# pink-0.net
KiCad netlist of a schematic drawn in EAGLE
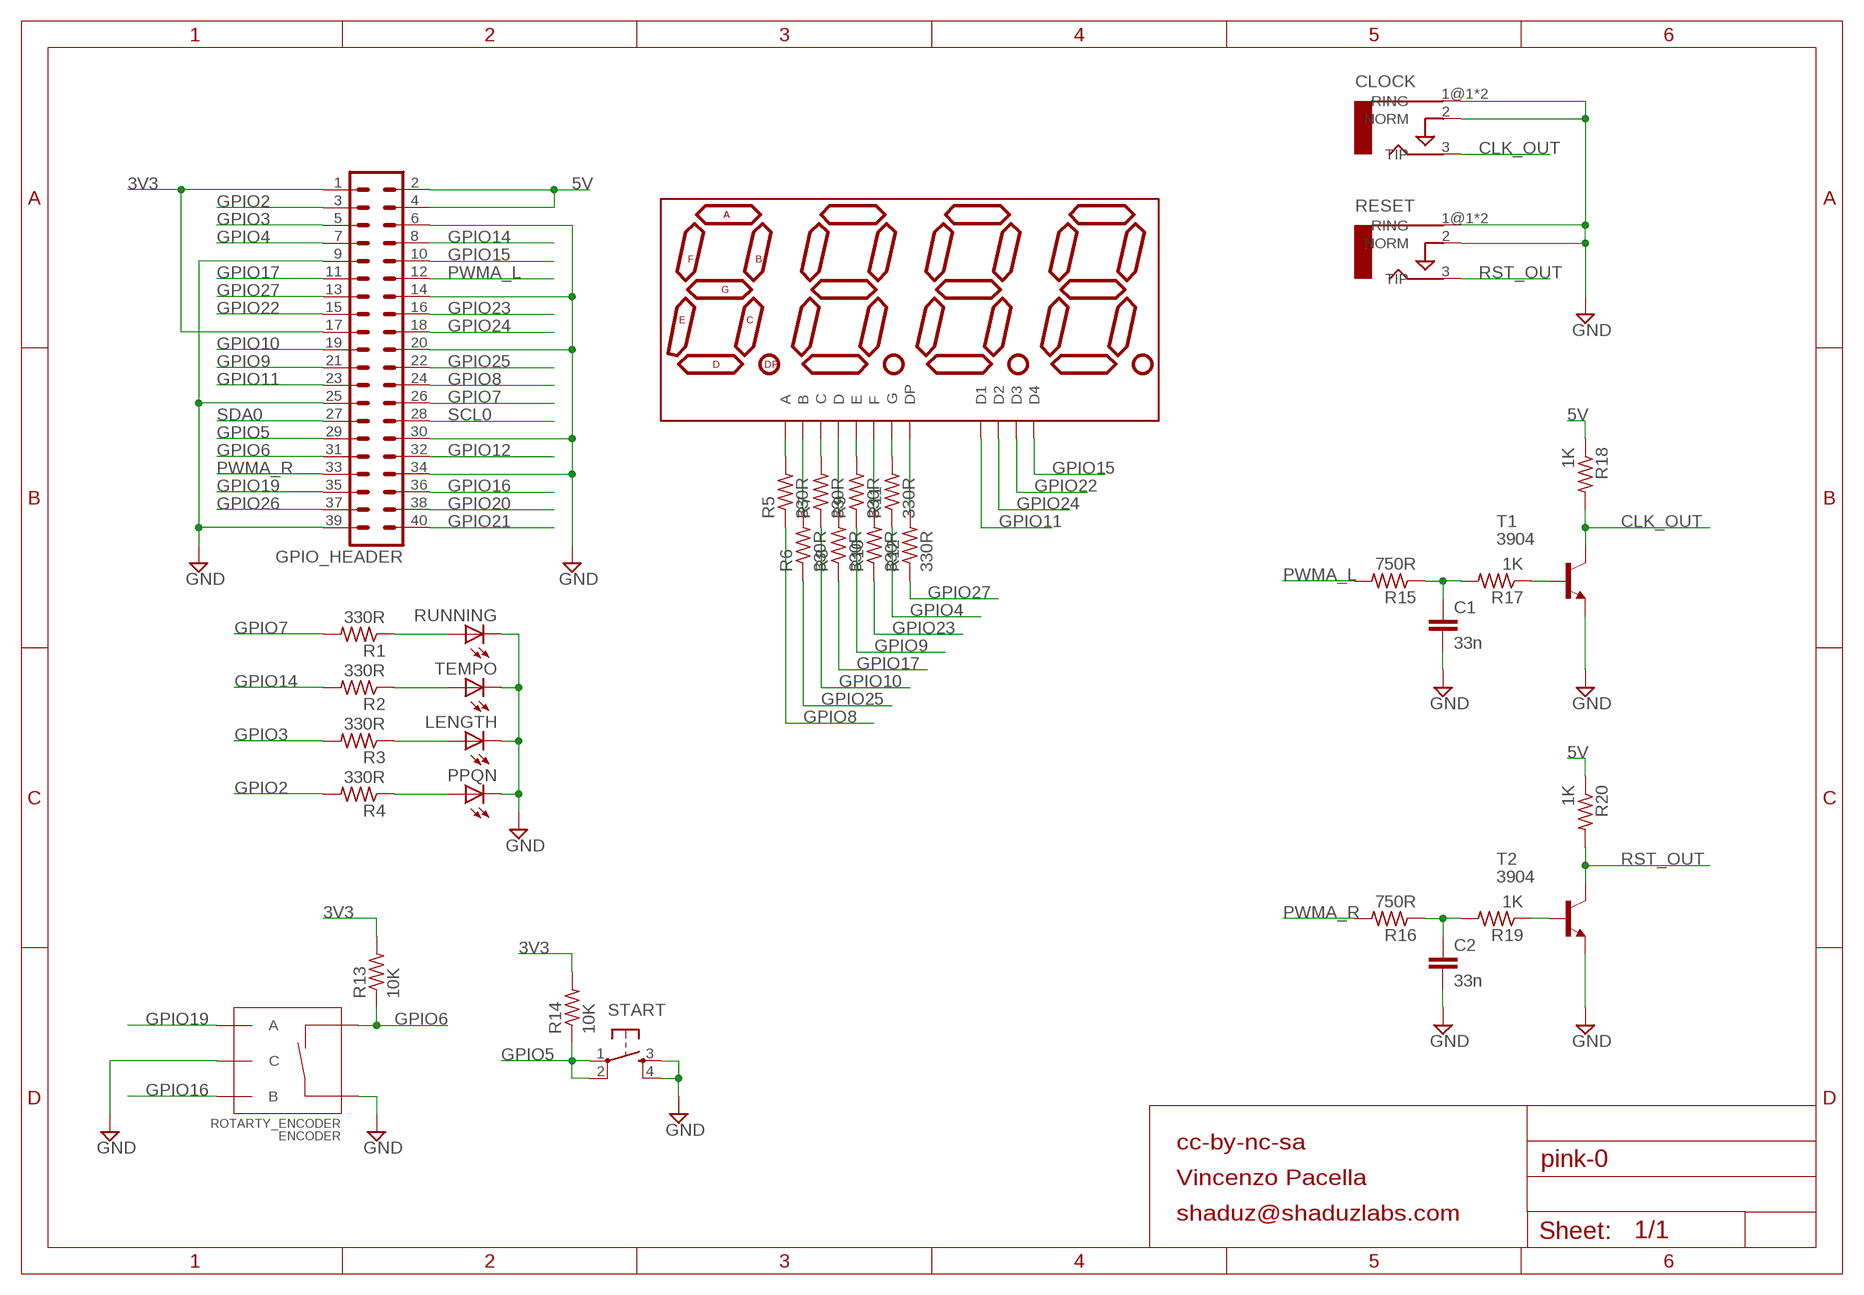
[diagram p0: schematic, sheet 1]

(export (version "E")
  (design (tool "Eeschema 10.0.6"))
  (components
    (comp (ref "C1")
      (value "33n")
      (footprint "eagle-import:0603-CAP")
      (libsource (lib "eagle-import") (part "CAP0603-CAP"))
    )
    (comp (ref "C2")
      (value "33n")
      (footprint "eagle-import:0603-CAP")
      (libsource (lib "eagle-import") (part "CAP0603-CAP"))
    )
    (comp (ref "CLOCK")
      (value "AUDIO-JACKERTHENVAR")
      (footprint "eagle-import:ERTHENVAR-JACK")
      (libsource (lib "eagle-import") (part "AUDIO-JACKERTHENVAR"))
    )
    (comp (ref "DISP1")
      (value "QDSP6064")
      (footprint "eagle-import:DIL12")
      (libsource (lib "eagle-import") (part "7-SEGMENT-4DIGIT-COUNTER-HP-BUBBLE"))
    )
    (comp (ref "ENCODER")
      (value "ROTARTY_ENCODER")
      (footprint "eagle-import:ROTARY_ENC_PLAIN")
      (libsource (lib "eagle-import") (part "ROTARTY_ENCODER"))
    )
    (comp (ref "GPIO_HEADER")
      (value "PIZERO_THROUGH_HOLE")
      (footprint "eagle-import:PIZERO_THOUGH_HOLE")
      (libsource (lib "eagle-import") (part "PIZERO_THROUGH_HOLE"))
    )
    (comp (ref "LENGTH")
      (value "LED0603")
      (footprint "eagle-import:LED-0603")
      (libsource (lib "eagle-import") (part "LED0603"))
    )
    (comp (ref "PPQN")
      (value "LED0603")
      (footprint "eagle-import:LED-0603")
      (libsource (lib "eagle-import") (part "LED0603"))
    )
    (comp (ref "R1")
      (value "330R")
      (footprint "eagle-import:R0402")
      (libsource (lib "eagle-import") (part "R-US_R0402"))
    )
    (comp (ref "R2")
      (value "330R")
      (footprint "eagle-import:R0402")
      (libsource (lib "eagle-import") (part "R-US_R0402"))
    )
    (comp (ref "R3")
      (value "330R")
      (footprint "eagle-import:R0402")
      (libsource (lib "eagle-import") (part "R-US_R0402"))
    )
    (comp (ref "R4")
      (value "330R")
      (footprint "eagle-import:R0402")
      (libsource (lib "eagle-import") (part "R-US_R0402"))
    )
    (comp (ref "R5")
      (value "330R")
      (footprint "eagle-import:R0402")
      (libsource (lib "eagle-import") (part "R-US_R0402"))
    )
    (comp (ref "R6")
      (value "330R")
      (footprint "eagle-import:R0402")
      (libsource (lib "eagle-import") (part "R-US_R0402"))
    )
    (comp (ref "R7")
      (value "330R")
      (footprint "eagle-import:R0402")
      (libsource (lib "eagle-import") (part "R-US_R0402"))
    )
    (comp (ref "R8")
      (value "330R")
      (footprint "eagle-import:R0402")
      (libsource (lib "eagle-import") (part "R-US_R0402"))
    )
    (comp (ref "R9")
      (value "330R")
      (footprint "eagle-import:R0402")
      (libsource (lib "eagle-import") (part "R-US_R0402"))
    )
    (comp (ref "R10")
      (value "330R")
      (footprint "eagle-import:R0402")
      (libsource (lib "eagle-import") (part "R-US_R0402"))
    )
    (comp (ref "R11")
      (value "330R")
      (footprint "eagle-import:R0402")
      (libsource (lib "eagle-import") (part "R-US_R0402"))
    )
    (comp (ref "R12")
      (value "330R")
      (footprint "eagle-import:R0402")
      (libsource (lib "eagle-import") (part "R-US_R0402"))
    )
    (comp (ref "R13")
      (value "10K")
      (footprint "eagle-import:R0402")
      (libsource (lib "eagle-import") (part "R-US_R0402"))
    )
    (comp (ref "R14")
      (value "10K")
      (footprint "eagle-import:R0402")
      (libsource (lib "eagle-import") (part "R-US_R0402"))
    )
    (comp (ref "R15")
      (value "750R")
      (footprint "eagle-import:R0402")
      (libsource (lib "eagle-import") (part "R-US_R0402"))
    )
    (comp (ref "R16")
      (value "750R")
      (footprint "eagle-import:R0402")
      (libsource (lib "eagle-import") (part "R-US_R0402"))
    )
    (comp (ref "R17")
      (value "1K")
      (footprint "eagle-import:R0402")
      (libsource (lib "eagle-import") (part "R-US_R0402"))
    )
    (comp (ref "R18")
      (value "1K")
      (footprint "eagle-import:R0402")
      (libsource (lib "eagle-import") (part "R-US_R0402"))
    )
    (comp (ref "R19")
      (value "1K")
      (footprint "eagle-import:R0402")
      (libsource (lib "eagle-import") (part "R-US_R0402"))
    )
    (comp (ref "R20")
      (value "1K")
      (footprint "eagle-import:R0402")
      (libsource (lib "eagle-import") (part "R-US_R0402"))
    )
    (comp (ref "RESET")
      (value "AUDIO-JACKERTHENVAR")
      (footprint "eagle-import:ERTHENVAR-JACK")
      (libsource (lib "eagle-import") (part "AUDIO-JACKERTHENVAR"))
    )
    (comp (ref "RUNNING")
      (value "LED0603")
      (footprint "eagle-import:LED-0603")
      (libsource (lib "eagle-import") (part "LED0603"))
    )
    (comp (ref "START")
      (value "TAC_SWITCHPTH")
      (footprint "eagle-import:TACTILE-PTH")
      (libsource (lib "eagle-import") (part "TAC_SWITCHPTH"))
    )
    (comp (ref "T1")
      (value "3904")
      (footprint "eagle-import:SOT23-BEC")
      (libsource (lib "eagle-import") (part "-NPN-SOT23-BECMMBT3904LT1"))
    )
    (comp (ref "T2")
      (value "3904")
      (footprint "eagle-import:SOT23-BEC")
      (libsource (lib "eagle-import") (part "-NPN-SOT23-BECMMBT3904LT1"))
    )
    (comp (ref "TEMPO")
      (value "LED0603")
      (footprint "eagle-import:LED-0603")
      (libsource (lib "eagle-import") (part "LED0603"))
    )
  )
  (nets
    (net (code "1") (name "/3V3") (class "Default")
      (node (ref "GPIO_HEADER") (pin "1") (pinfunction "1_1") (pintype "passive"))
      (node (ref "GPIO_HEADER") (pin "17") (pinfunction "17_17") (pintype "passive"))
      (node (ref "R13") (pin "2") (pinfunction "2_2") (pintype "passive"))
      (node (ref "R14") (pin "2") (pinfunction "2_2") (pintype "passive"))
    )
    (net (code "2") (name "/5V") (class "Default")
      (node (ref "GPIO_HEADER") (pin "2") (pinfunction "2_2") (pintype "passive"))
      (node (ref "GPIO_HEADER") (pin "4") (pinfunction "4_4") (pintype "passive"))
      (node (ref "R18") (pin "1") (pinfunction "1_1") (pintype "passive"))
      (node (ref "R20") (pin "1") (pinfunction "1_1") (pintype "passive"))
    )
    (net (code "3") (name "/CLK_OUT") (class "Default")
      (node (ref "CLOCK") (pin "3") (pinfunction "TIP_3") (pintype "bidirectional"))
      (node (ref "R18") (pin "2") (pinfunction "2_2") (pintype "passive"))
      (node (ref "T1") (pin "C") (pinfunction "C_C") (pintype "passive"))
    )
    (net (code "4") (name "/GPIO2") (class "Default")
      (node (ref "GPIO_HEADER") (pin "3") (pinfunction "3_3") (pintype "passive"))
      (node (ref "R4") (pin "2") (pinfunction "2_2") (pintype "passive"))
    )
    (net (code "5") (name "/GPIO3") (class "Default")
      (node (ref "GPIO_HEADER") (pin "5") (pinfunction "5_5") (pintype "passive"))
      (node (ref "R3") (pin "2") (pinfunction "2_2") (pintype "passive"))
    )
    (net (code "6") (name "/GPIO4") (class "Default")
      (node (ref "GPIO_HEADER") (pin "7") (pinfunction "7_7") (pintype "passive"))
      (node (ref "R11") (pin "1") (pinfunction "1_1") (pintype "passive"))
    )
    (net (code "7") (name "/GPIO5") (class "Default")
      (node (ref "GPIO_HEADER") (pin "29") (pinfunction "29_29") (pintype "passive"))
      (node (ref "R14") (pin "1") (pinfunction "1_1") (pintype "passive"))
      (node (ref "START") (pin "1") (pinfunction "1_1") (pintype "passive"))
      (node (ref "START") (pin "2") (pinfunction "2_2") (pintype "passive"))
    )
    (net (code "8") (name "/GPIO6") (class "Default")
      (node (ref "ENCODER") (pin "SW-") (pinfunction "SW-_SW-") (pintype "bidirectional"))
      (node (ref "GPIO_HEADER") (pin "31") (pinfunction "31_31") (pintype "passive"))
      (node (ref "R13") (pin "1") (pinfunction "1_1") (pintype "passive"))
    )
    (net (code "9") (name "/GPIO7") (class "Default")
      (node (ref "GPIO_HEADER") (pin "26") (pinfunction "26_26") (pintype "passive"))
      (node (ref "R1") (pin "2") (pinfunction "2_2") (pintype "passive"))
    )
    (net (code "10") (name "/GPIO8") (class "Default")
      (node (ref "GPIO_HEADER") (pin "24") (pinfunction "24_24") (pintype "passive"))
      (node (ref "R5") (pin "1") (pinfunction "1_1") (pintype "passive"))
    )
    (net (code "11") (name "/GPIO9") (class "Default")
      (node (ref "GPIO_HEADER") (pin "21") (pinfunction "21_21") (pintype "passive"))
      (node (ref "R9") (pin "1") (pinfunction "1_1") (pintype "passive"))
    )
    (net (code "12") (name "/GPIO10") (class "Default")
      (node (ref "GPIO_HEADER") (pin "19") (pinfunction "19_19") (pintype "passive"))
      (node (ref "R7") (pin "1") (pinfunction "1_1") (pintype "passive"))
    )
    (net (code "13") (name "/GPIO11") (class "Default")
      (node (ref "DISP1") (pin "1") (pinfunction "D1_1") (pintype "bidirectional"))
      (node (ref "GPIO_HEADER") (pin "23") (pinfunction "23_23") (pintype "passive"))
    )
    (net (code "14") (name "/GPIO12") (class "Default")
      (node (ref "GPIO_HEADER") (pin "32") (pinfunction "32_32") (pintype "passive"))
    )
    (net (code "15") (name "/GPIO14") (class "Default")
      (node (ref "GPIO_HEADER") (pin "8") (pinfunction "8_8") (pintype "passive"))
      (node (ref "R2") (pin "2") (pinfunction "2_2") (pintype "passive"))
    )
    (net (code "16") (name "/GPIO15") (class "Default")
      (node (ref "DISP1") (pin "6") (pinfunction "D4_6") (pintype "bidirectional"))
      (node (ref "GPIO_HEADER") (pin "10") (pinfunction "10_10") (pintype "passive"))
    )
    (net (code "17") (name "/GPIO16") (class "Default")
      (node (ref "ENCODER") (pin "B") (pinfunction "B_B") (pintype "bidirectional"))
      (node (ref "GPIO_HEADER") (pin "36") (pinfunction "36_36") (pintype "passive"))
    )
    (net (code "18") (name "/GPIO17") (class "Default")
      (node (ref "GPIO_HEADER") (pin "11") (pinfunction "11_11") (pintype "passive"))
      (node (ref "R8") (pin "1") (pinfunction "1_1") (pintype "passive"))
    )
    (net (code "19") (name "/GPIO19") (class "Default")
      (node (ref "ENCODER") (pin "A") (pinfunction "A_A") (pintype "bidirectional"))
      (node (ref "GPIO_HEADER") (pin "35") (pinfunction "35_35") (pintype "passive"))
    )
    (net (code "20") (name "/GPIO20") (class "Default")
      (node (ref "GPIO_HEADER") (pin "38") (pinfunction "38_38") (pintype "passive"))
    )
    (net (code "21") (name "/GPIO21") (class "Default")
      (node (ref "GPIO_HEADER") (pin "40") (pinfunction "40_40") (pintype "passive"))
    )
    (net (code "22") (name "/GPIO22") (class "Default")
      (node (ref "DISP1") (pin "4") (pinfunction "D3_4") (pintype "bidirectional"))
      (node (ref "GPIO_HEADER") (pin "15") (pinfunction "15_15") (pintype "passive"))
    )
    (net (code "23") (name "/GPIO23") (class "Default")
      (node (ref "GPIO_HEADER") (pin "16") (pinfunction "16_16") (pintype "passive"))
      (node (ref "R10") (pin "1") (pinfunction "1_1") (pintype "passive"))
    )
    (net (code "24") (name "/GPIO24") (class "Default")
      (node (ref "DISP1") (pin "10") (pinfunction "D2_10") (pintype "bidirectional"))
      (node (ref "GPIO_HEADER") (pin "18") (pinfunction "18_18") (pintype "passive"))
    )
    (net (code "25") (name "/GPIO25") (class "Default")
      (node (ref "GPIO_HEADER") (pin "22") (pinfunction "22_22") (pintype "passive"))
      (node (ref "R6") (pin "1") (pinfunction "1_1") (pintype "passive"))
    )
    (net (code "26") (name "/GPIO26") (class "Default")
      (node (ref "GPIO_HEADER") (pin "37") (pinfunction "37_37") (pintype "passive"))
    )
    (net (code "27") (name "/GPIO27") (class "Default")
      (node (ref "GPIO_HEADER") (pin "13") (pinfunction "13_13") (pintype "passive"))
      (node (ref "R12") (pin "1") (pinfunction "1_1") (pintype "passive"))
    )
    (net (code "28") (name "/PWMA_L") (class "Default")
      (node (ref "GPIO_HEADER") (pin "12") (pinfunction "12_12") (pintype "passive"))
      (node (ref "R15") (pin "2") (pinfunction "2_2") (pintype "passive"))
    )
    (net (code "29") (name "/PWMA_R") (class "Default")
      (node (ref "GPIO_HEADER") (pin "33") (pinfunction "33_33") (pintype "passive"))
      (node (ref "R16") (pin "2") (pinfunction "2_2") (pintype "passive"))
    )
    (net (code "30") (name "/RST_OUT") (class "Default")
      (node (ref "R20") (pin "2") (pinfunction "2_2") (pintype "passive"))
      (node (ref "RESET") (pin "3") (pinfunction "TIP_3") (pintype "bidirectional"))
      (node (ref "T2") (pin "C") (pinfunction "C_C") (pintype "passive"))
    )
    (net (code "31") (name "/SCL0") (class "Default")
      (node (ref "GPIO_HEADER") (pin "28") (pinfunction "28_28") (pintype "passive"))
    )
    (net (code "32") (name "/SDA0") (class "Default")
      (node (ref "GPIO_HEADER") (pin "27") (pinfunction "27_27") (pintype "passive"))
    )
    (net (code "33") (name "GND") (class "Default")
      (node (ref "C1") (pin "2") (pinfunction "2_2") (pintype "passive"))
      (node (ref "C2") (pin "2") (pinfunction "2_2") (pintype "passive"))
      (node (ref "CLOCK") (pin "1@1") (pinfunction "RING_1@1") (pintype "bidirectional"))
      (node (ref "CLOCK") (pin "1@2") (pinfunction "RING_1@2") (pintype "bidirectional"))
      (node (ref "CLOCK") (pin "2") (pinfunction "NORM_2") (pintype "bidirectional"))
      (node (ref "ENCODER") (pin "C") (pinfunction "C_C") (pintype "bidirectional"))
      (node (ref "ENCODER") (pin "SW+") (pinfunction "SW+_SW+") (pintype "bidirectional"))
      (node (ref "GPIO_HEADER") (pin "14") (pinfunction "14_14") (pintype "passive"))
      (node (ref "GPIO_HEADER") (pin "20") (pinfunction "20_20") (pintype "passive"))
      (node (ref "GPIO_HEADER") (pin "25") (pinfunction "25_25") (pintype "passive"))
      (node (ref "GPIO_HEADER") (pin "30") (pinfunction "30_30") (pintype "passive"))
      (node (ref "GPIO_HEADER") (pin "34") (pinfunction "34_34") (pintype "passive"))
      (node (ref "GPIO_HEADER") (pin "39") (pinfunction "39_39") (pintype "passive"))
      (node (ref "GPIO_HEADER") (pin "6") (pinfunction "6_6") (pintype "passive"))
      (node (ref "GPIO_HEADER") (pin "9") (pinfunction "9_9") (pintype "passive"))
      (node (ref "LENGTH") (pin "C") (pinfunction "C_C") (pintype "passive"))
      (node (ref "PPQN") (pin "C") (pinfunction "C_C") (pintype "passive"))
      (node (ref "RESET") (pin "1@1") (pinfunction "RING_1@1") (pintype "bidirectional"))
      (node (ref "RESET") (pin "1@2") (pinfunction "RING_1@2") (pintype "bidirectional"))
      (node (ref "RESET") (pin "2") (pinfunction "NORM_2") (pintype "bidirectional"))
      (node (ref "RUNNING") (pin "C") (pinfunction "C_C") (pintype "passive"))
      (node (ref "START") (pin "3") (pinfunction "3_3") (pintype "passive"))
      (node (ref "START") (pin "4") (pinfunction "4_4") (pintype "passive"))
      (node (ref "T1") (pin "E") (pinfunction "E_E") (pintype "passive"))
      (node (ref "T2") (pin "E") (pinfunction "E_E") (pintype "passive"))
      (node (ref "TEMPO") (pin "C") (pinfunction "C_C") (pintype "passive"))
    )
    (net (code "34") (name "Net-(C1-Pad1)") (class "Default")
      (node (ref "C1") (pin "1") (pinfunction "1_1") (pintype "passive"))
      (node (ref "R15") (pin "1") (pinfunction "1_1") (pintype "passive"))
      (node (ref "R17") (pin "2") (pinfunction "2_2") (pintype "passive"))
    )
    (net (code "35") (name "Net-(C2-Pad1)") (class "Default")
      (node (ref "C2") (pin "1") (pinfunction "1_1") (pintype "passive"))
      (node (ref "R16") (pin "1") (pinfunction "1_1") (pintype "passive"))
      (node (ref "R19") (pin "2") (pinfunction "2_2") (pintype "passive"))
    )
    (net (code "36") (name "Net-(DISP1-A)") (class "Default")
      (node (ref "DISP1") (pin "12") (pinfunction "A_12") (pintype "bidirectional"))
      (node (ref "R5") (pin "2") (pinfunction "2_2") (pintype "passive"))
    )
    (net (code "37") (name "Net-(DISP1-B)") (class "Default")
      (node (ref "DISP1") (pin "11") (pinfunction "B_11") (pintype "bidirectional"))
      (node (ref "R6") (pin "2") (pinfunction "2_2") (pintype "passive"))
    )
    (net (code "38") (name "Net-(DISP1-C)") (class "Default")
      (node (ref "DISP1") (pin "3") (pinfunction "C_3") (pintype "bidirectional"))
      (node (ref "R7") (pin "2") (pinfunction "2_2") (pintype "passive"))
    )
    (net (code "39") (name "Net-(DISP1-D)") (class "Default")
      (node (ref "DISP1") (pin "8") (pinfunction "D_8") (pintype "bidirectional"))
      (node (ref "R8") (pin "2") (pinfunction "2_2") (pintype "passive"))
    )
    (net (code "40") (name "Net-(DISP1-DP)") (class "Default")
      (node (ref "DISP1") (pin "5") (pinfunction "DP_5") (pintype "bidirectional"))
      (node (ref "R12") (pin "2") (pinfunction "2_2") (pintype "passive"))
    )
    (net (code "41") (name "Net-(DISP1-E)") (class "Default")
      (node (ref "DISP1") (pin "2") (pinfunction "E_2") (pintype "bidirectional"))
      (node (ref "R9") (pin "2") (pinfunction "2_2") (pintype "passive"))
    )
    (net (code "42") (name "Net-(DISP1-F)") (class "Default")
      (node (ref "DISP1") (pin "9") (pinfunction "F_9") (pintype "bidirectional"))
      (node (ref "R10") (pin "2") (pinfunction "2_2") (pintype "passive"))
    )
    (net (code "43") (name "Net-(DISP1-G)") (class "Default")
      (node (ref "DISP1") (pin "7") (pinfunction "G_7") (pintype "bidirectional"))
      (node (ref "R11") (pin "2") (pinfunction "2_2") (pintype "passive"))
    )
    (net (code "44") (name "Net-(LENGTH-PadA)") (class "Default")
      (node (ref "LENGTH") (pin "A") (pinfunction "A_A") (pintype "passive"))
      (node (ref "R3") (pin "1") (pinfunction "1_1") (pintype "passive"))
    )
    (net (code "45") (name "Net-(PPQN-PadA)") (class "Default")
      (node (ref "PPQN") (pin "A") (pinfunction "A_A") (pintype "passive"))
      (node (ref "R4") (pin "1") (pinfunction "1_1") (pintype "passive"))
    )
    (net (code "46") (name "Net-(R1-Pad1)") (class "Default")
      (node (ref "R1") (pin "1") (pinfunction "1_1") (pintype "passive"))
      (node (ref "RUNNING") (pin "A") (pinfunction "A_A") (pintype "passive"))
    )
    (net (code "47") (name "Net-(R2-Pad1)") (class "Default")
      (node (ref "R2") (pin "1") (pinfunction "1_1") (pintype "passive"))
      (node (ref "TEMPO") (pin "A") (pinfunction "A_A") (pintype "passive"))
    )
    (net (code "48") (name "Net-(R17-Pad1)") (class "Default")
      (node (ref "R17") (pin "1") (pinfunction "1_1") (pintype "passive"))
      (node (ref "T1") (pin "B") (pinfunction "B_B") (pintype "passive"))
    )
    (net (code "49") (name "Net-(R19-Pad1)") (class "Default")
      (node (ref "R19") (pin "1") (pinfunction "1_1") (pintype "passive"))
      (node (ref "T2") (pin "B") (pinfunction "B_B") (pintype "passive"))
    )
  )
)
